# RS485.net
KiCad netlist of a schematic drawn in Altium Designer
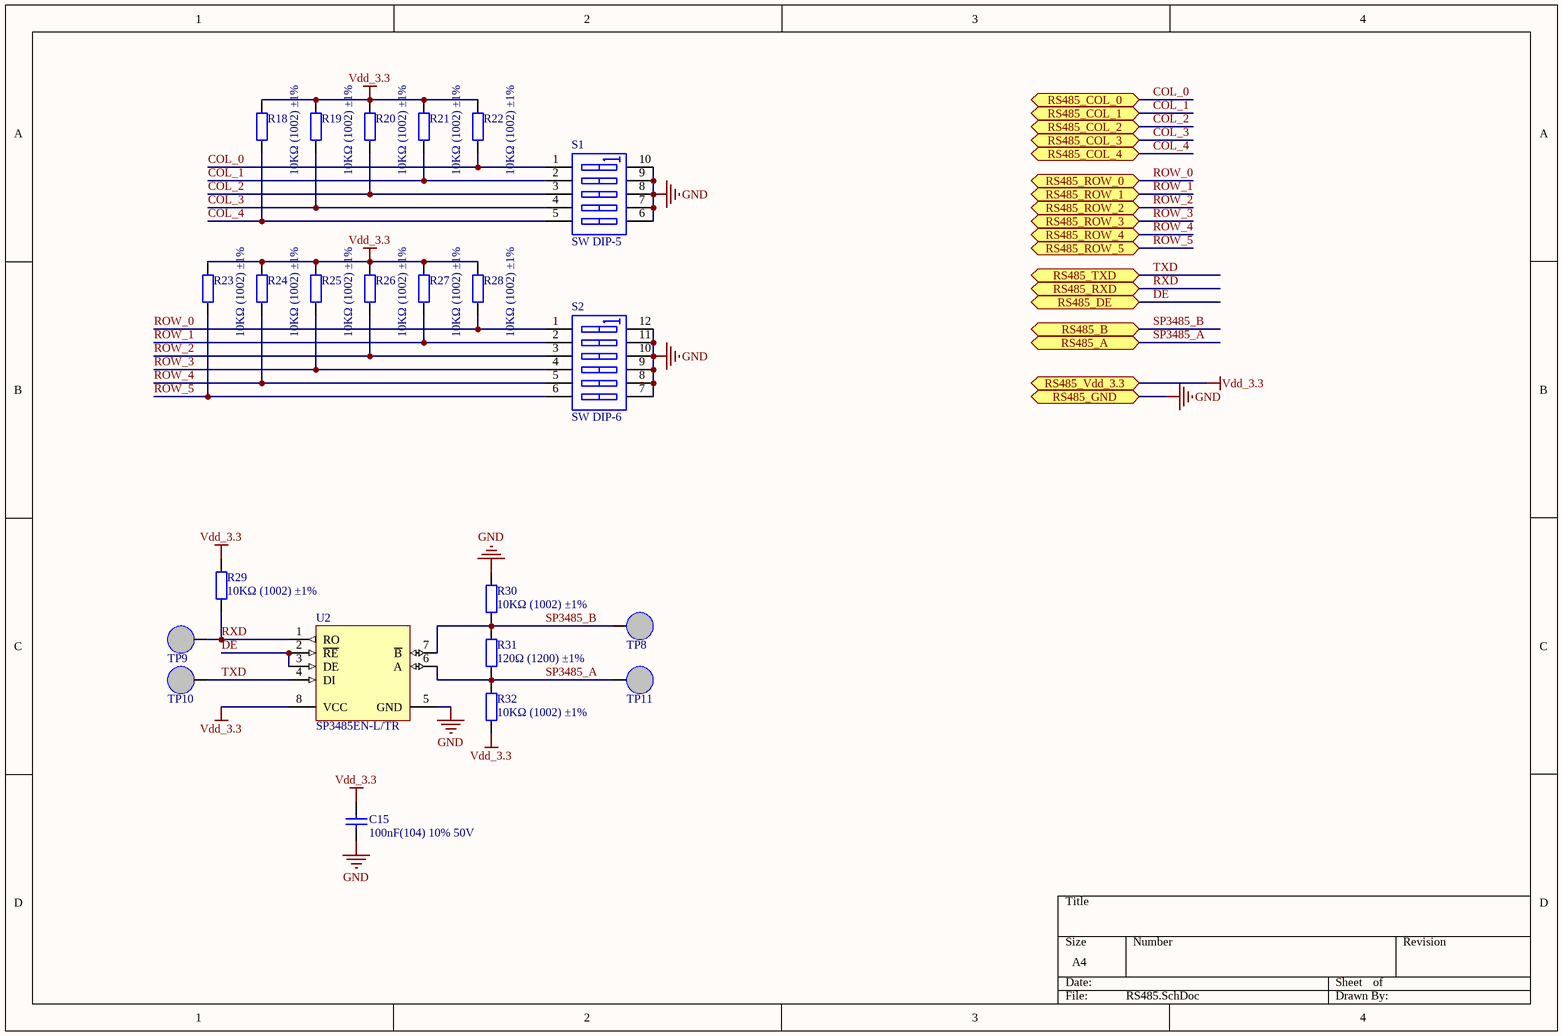
[diagram p0: RS485.SchDoc]

(export (version "E")
  (design (tool "Eeschema 10.0.6"))
  (components
    (comp (ref "C15")
      (value "100nF(104) 10% 50V")
      (footprint "0805_C")
      (description "贴片电容")
      (libsource (lib "Miscellaneous Devices LC") (part "0805 100nF(104) 10% 50V"))
    )
    (comp (ref "R18")
      (value "10KΩ (1002) ±1%")
      (footprint "0805_R")
      (description "贴片电阻")
      (libsource (lib "Miscellaneous Devices LC") (part "0805 10KΩ (1002) 1%"))
    )
    (comp (ref "R19")
      (value "10KΩ (1002) ±1%")
      (footprint "0805_R")
      (description "贴片电阻")
      (libsource (lib "Miscellaneous Devices LC") (part "0805 10KΩ (1002) 1%"))
    )
    (comp (ref "R20")
      (value "10KΩ (1002) ±1%")
      (footprint "0805_R")
      (description "贴片电阻")
      (libsource (lib "Miscellaneous Devices LC") (part "0805 10KΩ (1002) 1%"))
    )
    (comp (ref "R21")
      (value "10KΩ (1002) ±1%")
      (footprint "0805_R")
      (description "贴片电阻")
      (libsource (lib "Miscellaneous Devices LC") (part "0805 10KΩ (1002) 1%"))
    )
    (comp (ref "R22")
      (value "10KΩ (1002) ±1%")
      (footprint "0805_R")
      (description "贴片电阻")
      (libsource (lib "Miscellaneous Devices LC") (part "0805 10KΩ (1002) 1%"))
    )
    (comp (ref "R23")
      (value "10KΩ (1002) ±1%")
      (footprint "0805_R")
      (description "贴片电阻")
      (libsource (lib "Miscellaneous Devices LC") (part "0805 10KΩ (1002) 1%"))
    )
    (comp (ref "R24")
      (value "10KΩ (1002) ±1%")
      (footprint "0805_R")
      (description "贴片电阻")
      (libsource (lib "Miscellaneous Devices LC") (part "0805 10KΩ (1002) 1%"))
    )
    (comp (ref "R25")
      (value "10KΩ (1002) ±1%")
      (footprint "0805_R")
      (description "贴片电阻")
      (libsource (lib "Miscellaneous Devices LC") (part "0805 10KΩ (1002) 1%"))
    )
    (comp (ref "R26")
      (value "10KΩ (1002) ±1%")
      (footprint "0805_R")
      (description "贴片电阻")
      (libsource (lib "Miscellaneous Devices LC") (part "0805 10KΩ (1002) 1%"))
    )
    (comp (ref "R27")
      (value "10KΩ (1002) ±1%")
      (footprint "0805_R")
      (description "贴片电阻")
      (libsource (lib "Miscellaneous Devices LC") (part "0805 10KΩ (1002) 1%"))
    )
    (comp (ref "R28")
      (value "10KΩ (1002) ±1%")
      (footprint "0805_R")
      (description "贴片电阻")
      (libsource (lib "Miscellaneous Devices LC") (part "0805 10KΩ (1002) 1%"))
    )
    (comp (ref "R29")
      (value "10KΩ (1002) ±1%")
      (footprint "0805_R")
      (description "贴片电阻")
      (libsource (lib "Miscellaneous Devices LC") (part "0805 10KΩ (1002) 1%"))
    )
    (comp (ref "R30")
      (value "10KΩ (1002) ±1%")
      (footprint "0805_R")
      (description "贴片电阻")
      (libsource (lib "Miscellaneous Devices LC") (part "0805 10KΩ (1002) 1%"))
    )
    (comp (ref "R31")
      (value "120Ω (1200) ±1%")
      (footprint "0805_R")
      (description "贴片电阻")
      (libsource (lib "Miscellaneous Devices LC") (part "0805 120Ω (1200) 1%"))
    )
    (comp (ref "R32")
      (value "10KΩ (1002) ±1%")
      (footprint "0805_R")
      (description "贴片电阻")
      (libsource (lib "Miscellaneous Devices LC") (part "0805 10KΩ (1002) 1%"))
    )
    (comp (ref "S1")
      (value "SW DIP-5")
      (footprint "N10A")
      (description "DIP Switch, 5 Position, SPST")
      (fields (field (name "PUBLISHER") "Altium Limited"))
      (libsource (lib "Miscellaneous Devices") (part "SW DIP-5"))
    )
    (comp (ref "S2")
      (value "SW DIP-6")
      (footprint "DIP-12/SW")
      (description "DIP Switch, 6 Position, SPST")
      (fields (field (name "PUBLISHER") "Altium Limited"))
      (libsource (lib "Miscellaneous Devices") (part "SW DIP-6"))
    )
    (comp (ref "TP8") (value "TP") (footprint "TP") (libsource (lib "mylib") (part "TP")))
    (comp (ref "TP9") (value "TP") (footprint "TP") (libsource (lib "mylib") (part "TP")))
    (comp (ref "TP10") (value "TP") (footprint "TP") (libsource (lib "mylib") (part "TP")))
    (comp (ref "TP11") (value "TP") (footprint "TP") (libsource (lib "mylib") (part "TP")))
    (comp (ref "U2")
      (value "SP3485EN-L/TR")
      (footprint "SOIC-8_150mil")
      (description "RS-485/RS-422")
      (libsource (lib "Miscellaneous Devices LC") (part "SP3485EN-L/TR_[C8963]"))
    )
  )
  (nets
    (net (code "1") (name "/COL_0") (class "Default")
      (node (ref "R22") (pin "1") (pinfunction "1_1") (pintype "passive"))
      (node (ref "S1") (pin "1") (pinfunction "A1_1") (pintype "passive"))
    )
    (net (code "2") (name "/COL_1") (class "Default")
      (node (ref "R21") (pin "1") (pinfunction "1_1") (pintype "passive"))
      (node (ref "S1") (pin "2") (pinfunction "A2_2") (pintype "passive"))
    )
    (net (code "3") (name "/COL_2") (class "Default")
      (node (ref "R20") (pin "1") (pinfunction "1_1") (pintype "passive"))
      (node (ref "S1") (pin "3") (pinfunction "A3_3") (pintype "passive"))
    )
    (net (code "4") (name "/COL_3") (class "Default")
      (node (ref "R19") (pin "1") (pinfunction "1_1") (pintype "passive"))
      (node (ref "S1") (pin "4") (pinfunction "A4_4") (pintype "passive"))
    )
    (net (code "5") (name "/COL_4") (class "Default")
      (node (ref "R18") (pin "1") (pinfunction "1_1") (pintype "passive"))
      (node (ref "S1") (pin "5") (pinfunction "A5_5") (pintype "passive"))
    )
    (net (code "6") (name "/DE") (class "Default")
      (node (ref "U2") (pin "2") (pinfunction "~{RE}_2") (pintype "input"))
      (node (ref "U2") (pin "3") (pinfunction "DE_3") (pintype "input"))
    )
    (net (code "7") (name "/ROW_0") (class "Default")
      (node (ref "R28") (pin "1") (pinfunction "1_1") (pintype "passive"))
      (node (ref "S2") (pin "1") (pinfunction "A1_1") (pintype "passive"))
    )
    (net (code "8") (name "/ROW_1") (class "Default")
      (node (ref "R27") (pin "1") (pinfunction "1_1") (pintype "passive"))
      (node (ref "S2") (pin "2") (pinfunction "A2_2") (pintype "passive"))
    )
    (net (code "9") (name "/ROW_2") (class "Default")
      (node (ref "R26") (pin "1") (pinfunction "1_1") (pintype "passive"))
      (node (ref "S2") (pin "3") (pinfunction "A3_3") (pintype "passive"))
    )
    (net (code "10") (name "/ROW_3") (class "Default")
      (node (ref "R25") (pin "1") (pinfunction "1_1") (pintype "passive"))
      (node (ref "S2") (pin "4") (pinfunction "A4_4") (pintype "passive"))
    )
    (net (code "11") (name "/ROW_4") (class "Default")
      (node (ref "R24") (pin "1") (pinfunction "1_1") (pintype "passive"))
      (node (ref "S2") (pin "5") (pinfunction "A5_5") (pintype "passive"))
    )
    (net (code "12") (name "/ROW_5") (class "Default")
      (node (ref "R23") (pin "1") (pinfunction "1_1") (pintype "passive"))
      (node (ref "S2") (pin "6") (pinfunction "A6_6") (pintype "passive"))
    )
    (net (code "13") (name "/RXD") (class "Default")
      (node (ref "R29") (pin "1") (pinfunction "1_1") (pintype "passive"))
      (node (ref "TP9") (pin "1") (pinfunction "1_1") (pintype "passive"))
      (node (ref "U2") (pin "1") (pinfunction "RO_1") (pintype "output"))
    )
    (net (code "14") (name "/SP3485_A") (class "Default")
      (node (ref "R31") (pin "1") (pinfunction "1_1") (pintype "passive"))
      (node (ref "R32") (pin "2") (pinfunction "2_2") (pintype "passive"))
      (node (ref "TP11") (pin "1") (pinfunction "1_1") (pintype "passive"))
      (node (ref "U2") (pin "6") (pinfunction "A_6") (pintype "bidirectional"))
    )
    (net (code "15") (name "/SP3485_B") (class "Default")
      (node (ref "R30") (pin "1") (pinfunction "1_1") (pintype "passive"))
      (node (ref "R31") (pin "2") (pinfunction "2_2") (pintype "passive"))
      (node (ref "TP8") (pin "1") (pinfunction "1_1") (pintype "passive"))
      (node (ref "U2") (pin "7") (pinfunction "~{B}_7") (pintype "bidirectional"))
    )
    (net (code "16") (name "/TXD") (class "Default")
      (node (ref "TP10") (pin "1") (pinfunction "1_1") (pintype "passive"))
      (node (ref "U2") (pin "4") (pinfunction "DI_4") (pintype "input"))
    )
    (net (code "17") (name "GND") (class "Default")
      (node (ref "C15") (pin "2") (pinfunction "2_2") (pintype "passive"))
      (node (ref "R30") (pin "2") (pinfunction "2_2") (pintype "passive"))
      (node (ref "S1") (pin "10") (pinfunction "B1_10") (pintype "passive"))
      (node (ref "S1") (pin "6") (pinfunction "B5_6") (pintype "passive"))
      (node (ref "S1") (pin "7") (pinfunction "B4_7") (pintype "passive"))
      (node (ref "S1") (pin "8") (pinfunction "B3_8") (pintype "passive"))
      (node (ref "S1") (pin "9") (pinfunction "B2_9") (pintype "passive"))
      (node (ref "S2") (pin "10") (pinfunction "B3_10") (pintype "passive"))
      (node (ref "S2") (pin "11") (pinfunction "B2_11") (pintype "passive"))
      (node (ref "S2") (pin "12") (pinfunction "B1_12") (pintype "passive"))
      (node (ref "S2") (pin "7") (pinfunction "B6_7") (pintype "passive"))
      (node (ref "S2") (pin "8") (pinfunction "B5_8") (pintype "passive"))
      (node (ref "S2") (pin "9") (pinfunction "B4_9") (pintype "passive"))
      (node (ref "U2") (pin "5") (pinfunction "GND_5") (pintype "power_in"))
    )
    (net (code "18") (name "Vdd_3.3") (class "Default")
      (node (ref "C15") (pin "1") (pinfunction "1_1") (pintype "passive"))
      (node (ref "R18") (pin "2") (pinfunction "2_2") (pintype "passive"))
      (node (ref "R19") (pin "2") (pinfunction "2_2") (pintype "passive"))
      (node (ref "R20") (pin "2") (pinfunction "2_2") (pintype "passive"))
      (node (ref "R21") (pin "2") (pinfunction "2_2") (pintype "passive"))
      (node (ref "R22") (pin "2") (pinfunction "2_2") (pintype "passive"))
      (node (ref "R23") (pin "2") (pinfunction "2_2") (pintype "passive"))
      (node (ref "R24") (pin "2") (pinfunction "2_2") (pintype "passive"))
      (node (ref "R25") (pin "2") (pinfunction "2_2") (pintype "passive"))
      (node (ref "R26") (pin "2") (pinfunction "2_2") (pintype "passive"))
      (node (ref "R27") (pin "2") (pinfunction "2_2") (pintype "passive"))
      (node (ref "R28") (pin "2") (pinfunction "2_2") (pintype "passive"))
      (node (ref "R29") (pin "2") (pinfunction "2_2") (pintype "passive"))
      (node (ref "R32") (pin "1") (pinfunction "1_1") (pintype "passive"))
      (node (ref "U2") (pin "8") (pinfunction "VCC_8") (pintype "power_in"))
    )
  )
)
